# N64_RGBAmp.net
KiCad netlist of a schematic drawn in EAGLE
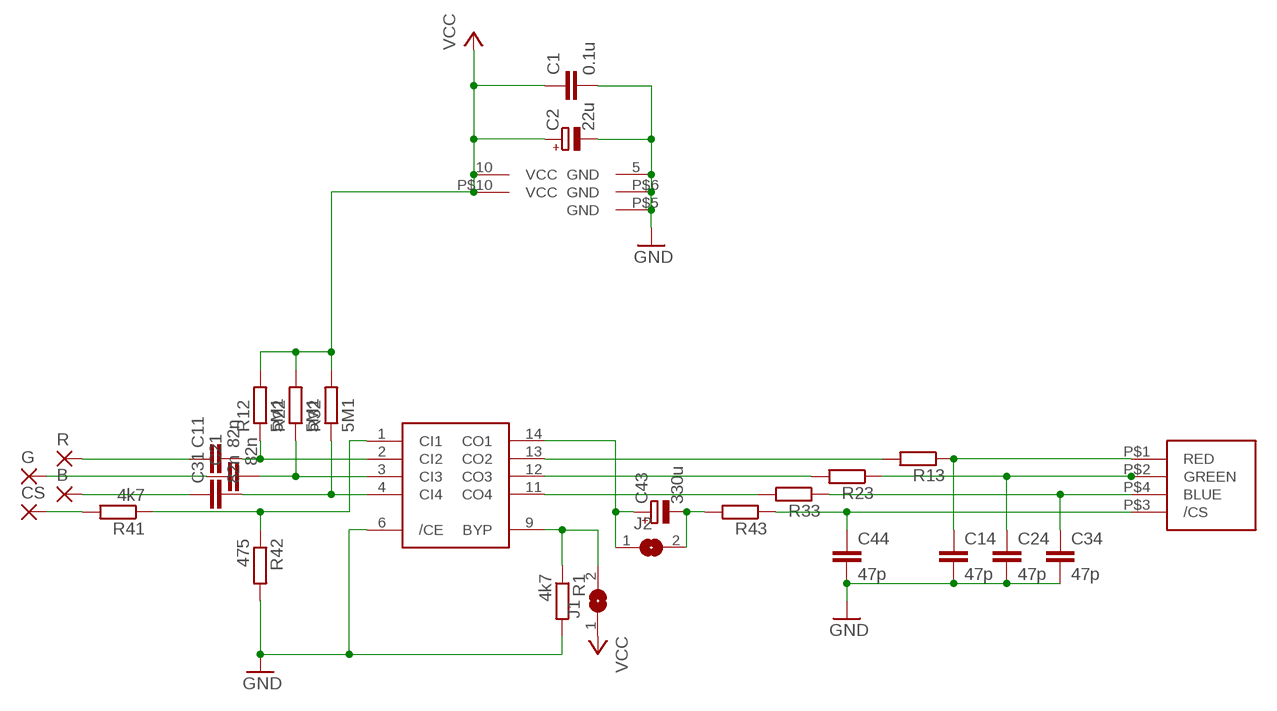
[diagram p0: schematic, sheet 1]

(export (version "E")
  (design (tool "Eeschema 10.0.6"))
  (components
    (comp (ref "B")
      (value "SMD2")
      (footprint "eagle-import:SMD1,27-2,54")
      (libsource (lib "eagle-import") (part "SMD2"))
    )
    (comp (ref "C1")
      (value "0.1u")
      (footprint "eagle-import:C0603K")
      (libsource (lib "eagle-import") (part "C-EUC0603K"))
    )
    (comp (ref "C2")
      (value "22u")
      (footprint "eagle-import:SMC_B")
      (libsource (lib "eagle-import") (part "CPOL-EUSMCB"))
    )
    (comp (ref "C11")
      (value "82n")
      (footprint "eagle-import:C0603K")
      (libsource (lib "eagle-import") (part "C-EUC0603K"))
    )
    (comp (ref "C14")
      (value "47p")
      (footprint "eagle-import:C0603K")
      (libsource (lib "eagle-import") (part "C-EUC0603K"))
    )
    (comp (ref "C21")
      (value "82n")
      (footprint "eagle-import:C0603K")
      (libsource (lib "eagle-import") (part "C-EUC0603K"))
    )
    (comp (ref "C24")
      (value "47p")
      (footprint "eagle-import:C0603K")
      (libsource (lib "eagle-import") (part "C-EUC0603K"))
    )
    (comp (ref "C31")
      (value "82n")
      (footprint "eagle-import:C0603K")
      (libsource (lib "eagle-import") (part "C-EUC0603K"))
    )
    (comp (ref "C34")
      (value "47p")
      (footprint "eagle-import:C0603K")
      (libsource (lib "eagle-import") (part "C-EUC0603K"))
    )
    (comp (ref "C43")
      (value "330u")
      (footprint "eagle-import:SMC_D")
      (libsource (lib "eagle-import") (part "CPOL-EUSMCD"))
    )
    (comp (ref "C44")
      (value "47p")
      (footprint "eagle-import:C0603K")
      (libsource (lib "eagle-import") (part "C-EUC0603K"))
    )
    (comp (ref "CS")
      (value "SMD2")
      (footprint "eagle-import:SMD1,27-2,54")
      (libsource (lib "eagle-import") (part "SMD2"))
    )
    (comp (ref "G")
      (value "SMD2")
      (footprint "eagle-import:SMD1,27-2,54")
      (libsource (lib "eagle-import") (part "SMD2"))
    )
    (comp (ref "J1") (value "SJ") (footprint "eagle-import:SJ") (libsource (lib "eagle-import") (part "SJ")))
    (comp (ref "J2") (value "SJ") (footprint "eagle-import:SJ") (libsource (lib "eagle-import") (part "SJ")))
    (comp (ref "J3")
      (value "SNES_MULTIAV_RGBC_ONLY")
      (footprint "eagle-import:SNES_MULTIAV_RGBC_ONLY")
      (libsource (lib "eagle-import") (part "SNES_MULTIAV_RGBC_ONLY"))
    )
    (comp (ref "R")
      (value "SMD2")
      (footprint "eagle-import:SMD1,27-2,54")
      (libsource (lib "eagle-import") (part "SMD2"))
    )
    (comp (ref "R1")
      (value "4k7")
      (footprint "eagle-import:R0603")
      (libsource (lib "eagle-import") (part "R-EU_R0603"))
    )
    (comp (ref "R12")
      (value "5M1")
      (footprint "eagle-import:R0603")
      (libsource (lib "eagle-import") (part "R-EU_R0603"))
    )
    (comp (ref "R13")
      (value "R-EU_R0603")
      (footprint "eagle-import:R0603")
      (libsource (lib "eagle-import") (part "R-EU_R0603"))
    )
    (comp (ref "R22")
      (value "5M1")
      (footprint "eagle-import:R0603")
      (libsource (lib "eagle-import") (part "R-EU_R0603"))
    )
    (comp (ref "R23")
      (value "R-EU_R0603")
      (footprint "eagle-import:R0603")
      (libsource (lib "eagle-import") (part "R-EU_R0603"))
    )
    (comp (ref "R32")
      (value "5M1")
      (footprint "eagle-import:R0603")
      (libsource (lib "eagle-import") (part "R-EU_R0603"))
    )
    (comp (ref "R33")
      (value "R-EU_R0603")
      (footprint "eagle-import:R0603")
      (libsource (lib "eagle-import") (part "R-EU_R0603"))
    )
    (comp (ref "R41")
      (value "4k7")
      (footprint "eagle-import:R0603")
      (libsource (lib "eagle-import") (part "R-EU_R0603"))
    )
    (comp (ref "R42")
      (value "475")
      (footprint "eagle-import:R0603")
      (libsource (lib "eagle-import") (part "R-EU_R0603"))
    )
    (comp (ref "R43")
      (value "R-EU_R0603")
      (footprint "eagle-import:R0603")
      (libsource (lib "eagle-import") (part "R-EU_R0603"))
    )
    (comp (ref "U1")
      (value "THS7374")
      (footprint "eagle-import:THS7374")
      (libsource (lib "eagle-import") (part "THS7374"))
    )
  )
  (nets
    (net (code "1") (name "GND") (class "Default")
      (node (ref "C1") (pin "2") (pinfunction "2_2") (pintype "passive"))
      (node (ref "C14") (pin "2") (pinfunction "2_2") (pintype "passive"))
      (node (ref "C2") (pin "-") (pinfunction "-_-") (pintype "passive"))
      (node (ref "C24") (pin "2") (pinfunction "2_2") (pintype "passive"))
      (node (ref "C34") (pin "2") (pinfunction "2_2") (pintype "passive"))
      (node (ref "C44") (pin "2") (pinfunction "2_2") (pintype "passive"))
      (node (ref "J3") (pin "P$5") (pinfunction "GND_P$5") (pintype "bidirectional"))
      (node (ref "J3") (pin "P$6") (pinfunction "GND_P$6") (pintype "bidirectional"))
      (node (ref "R1") (pin "2") (pinfunction "2_2") (pintype "passive"))
      (node (ref "R42") (pin "2") (pinfunction "2_2") (pintype "passive"))
      (node (ref "U1") (pin "5") (pinfunction "GND_5") (pintype "bidirectional"))
      (node (ref "U1") (pin "6") (pinfunction "/CE_6") (pintype "bidirectional"))
    )
    (net (code "2") (name "Net-(B-P)") (class "Default")
      (node (ref "B") (pin "1") (pinfunction "P_1") (pintype "passive"))
      (node (ref "C31") (pin "1") (pinfunction "1_1") (pintype "passive"))
    )
    (net (code "3") (name "Net-(C43-Pad-)") (class "Default")
      (node (ref "C43") (pin "-") (pinfunction "-_-") (pintype "passive"))
      (node (ref "J2") (pin "2") (pinfunction "2_2") (pintype "passive"))
      (node (ref "R43") (pin "2") (pinfunction "2_2") (pintype "passive"))
    )
    (net (code "4") (name "Net-(CS-P)") (class "Default")
      (node (ref "CS") (pin "1") (pinfunction "P_1") (pintype "passive"))
      (node (ref "R41") (pin "2") (pinfunction "2_2") (pintype "passive"))
    )
    (net (code "5") (name "Net-(G-P)") (class "Default")
      (node (ref "C21") (pin "1") (pinfunction "1_1") (pintype "passive"))
      (node (ref "G") (pin "1") (pinfunction "P_1") (pintype "passive"))
    )
    (net (code "6") (name "Net-(J3A-BLUE)") (class "Default")
      (node (ref "C34") (pin "1") (pinfunction "1_1") (pintype "passive"))
      (node (ref "J3") (pin "P$4") (pinfunction "BLUE_P$4") (pintype "bidirectional"))
      (node (ref "R33") (pin "1") (pinfunction "1_1") (pintype "passive"))
    )
    (net (code "7") (name "Net-(J3A-GREEN)") (class "Default")
      (node (ref "C24") (pin "1") (pinfunction "1_1") (pintype "passive"))
      (node (ref "J3") (pin "P$2") (pinfunction "GREEN_P$2") (pintype "bidirectional"))
      (node (ref "R23") (pin "1") (pinfunction "1_1") (pintype "passive"))
    )
    (net (code "8") (name "Net-(J3A-RED)") (class "Default")
      (node (ref "C14") (pin "1") (pinfunction "1_1") (pintype "passive"))
      (node (ref "J3") (pin "P$1") (pinfunction "RED_P$1") (pintype "bidirectional"))
      (node (ref "R13") (pin "1") (pinfunction "1_1") (pintype "passive"))
    )
    (net (code "9") (name "Net-(J3A-{slash}CS)") (class "Default")
      (node (ref "C44") (pin "1") (pinfunction "1_1") (pintype "passive"))
      (node (ref "J3") (pin "P$3") (pinfunction "/CS_P$3") (pintype "bidirectional"))
      (node (ref "R43") (pin "1") (pinfunction "1_1") (pintype "passive"))
    )
    (net (code "10") (name "Net-(R-P)") (class "Default")
      (node (ref "C11") (pin "1") (pinfunction "1_1") (pintype "passive"))
      (node (ref "R") (pin "1") (pinfunction "P_1") (pintype "passive"))
    )
    (net (code "11") (name "Net-(U1A-BYP)") (class "Default")
      (node (ref "J1") (pin "2") (pinfunction "2_2") (pintype "passive"))
      (node (ref "R1") (pin "1") (pinfunction "1_1") (pintype "passive"))
      (node (ref "U1") (pin "9") (pinfunction "BYP_9") (pintype "bidirectional"))
    )
    (net (code "12") (name "Net-(U1A-CI1)") (class "Default")
      (node (ref "R41") (pin "1") (pinfunction "1_1") (pintype "passive"))
      (node (ref "R42") (pin "1") (pinfunction "1_1") (pintype "passive"))
      (node (ref "U1") (pin "1") (pinfunction "CI1_1") (pintype "bidirectional"))
    )
    (net (code "13") (name "Net-(U1A-CI2)") (class "Default")
      (node (ref "C11") (pin "2") (pinfunction "2_2") (pintype "passive"))
      (node (ref "R12") (pin "1") (pinfunction "1_1") (pintype "passive"))
      (node (ref "U1") (pin "2") (pinfunction "CI2_2") (pintype "bidirectional"))
    )
    (net (code "14") (name "Net-(U1A-CI3)") (class "Default")
      (node (ref "C21") (pin "2") (pinfunction "2_2") (pintype "passive"))
      (node (ref "R22") (pin "1") (pinfunction "1_1") (pintype "passive"))
      (node (ref "U1") (pin "3") (pinfunction "CI3_3") (pintype "bidirectional"))
    )
    (net (code "15") (name "Net-(U1A-CI4)") (class "Default")
      (node (ref "C31") (pin "2") (pinfunction "2_2") (pintype "passive"))
      (node (ref "R32") (pin "1") (pinfunction "1_1") (pintype "passive"))
      (node (ref "U1") (pin "4") (pinfunction "CI4_4") (pintype "bidirectional"))
    )
    (net (code "16") (name "Net-(U1A-CO1)") (class "Default")
      (node (ref "C43") (pin "+") (pinfunction "+_+") (pintype "passive"))
      (node (ref "J2") (pin "1") (pinfunction "1_1") (pintype "passive"))
      (node (ref "U1") (pin "14") (pinfunction "CO1_14") (pintype "bidirectional"))
    )
    (net (code "17") (name "Net-(U1A-CO2)") (class "Default")
      (node (ref "R13") (pin "2") (pinfunction "2_2") (pintype "passive"))
      (node (ref "U1") (pin "13") (pinfunction "CO2_13") (pintype "bidirectional"))
    )
    (net (code "18") (name "Net-(U1A-CO3)") (class "Default")
      (node (ref "R23") (pin "2") (pinfunction "2_2") (pintype "passive"))
      (node (ref "U1") (pin "12") (pinfunction "CO3_12") (pintype "bidirectional"))
    )
    (net (code "19") (name "Net-(U1A-CO4)") (class "Default")
      (node (ref "R33") (pin "2") (pinfunction "2_2") (pintype "passive"))
      (node (ref "U1") (pin "11") (pinfunction "CO4_11") (pintype "bidirectional"))
    )
    (net (code "20") (name "VCC") (class "Default")
      (node (ref "C1") (pin "1") (pinfunction "1_1") (pintype "passive"))
      (node (ref "C2") (pin "+") (pinfunction "+_+") (pintype "passive"))
      (node (ref "J1") (pin "1") (pinfunction "1_1") (pintype "passive"))
      (node (ref "J3") (pin "P$10") (pinfunction "VCC_P$10") (pintype "bidirectional"))
      (node (ref "R12") (pin "2") (pinfunction "2_2") (pintype "passive"))
      (node (ref "R22") (pin "2") (pinfunction "2_2") (pintype "passive"))
      (node (ref "R32") (pin "2") (pinfunction "2_2") (pintype "passive"))
      (node (ref "U1") (pin "10") (pinfunction "VCC_10") (pintype "bidirectional"))
    )
  )
)
